# 4G.net
KiCad netlist of a schematic drawn in Altium Designer
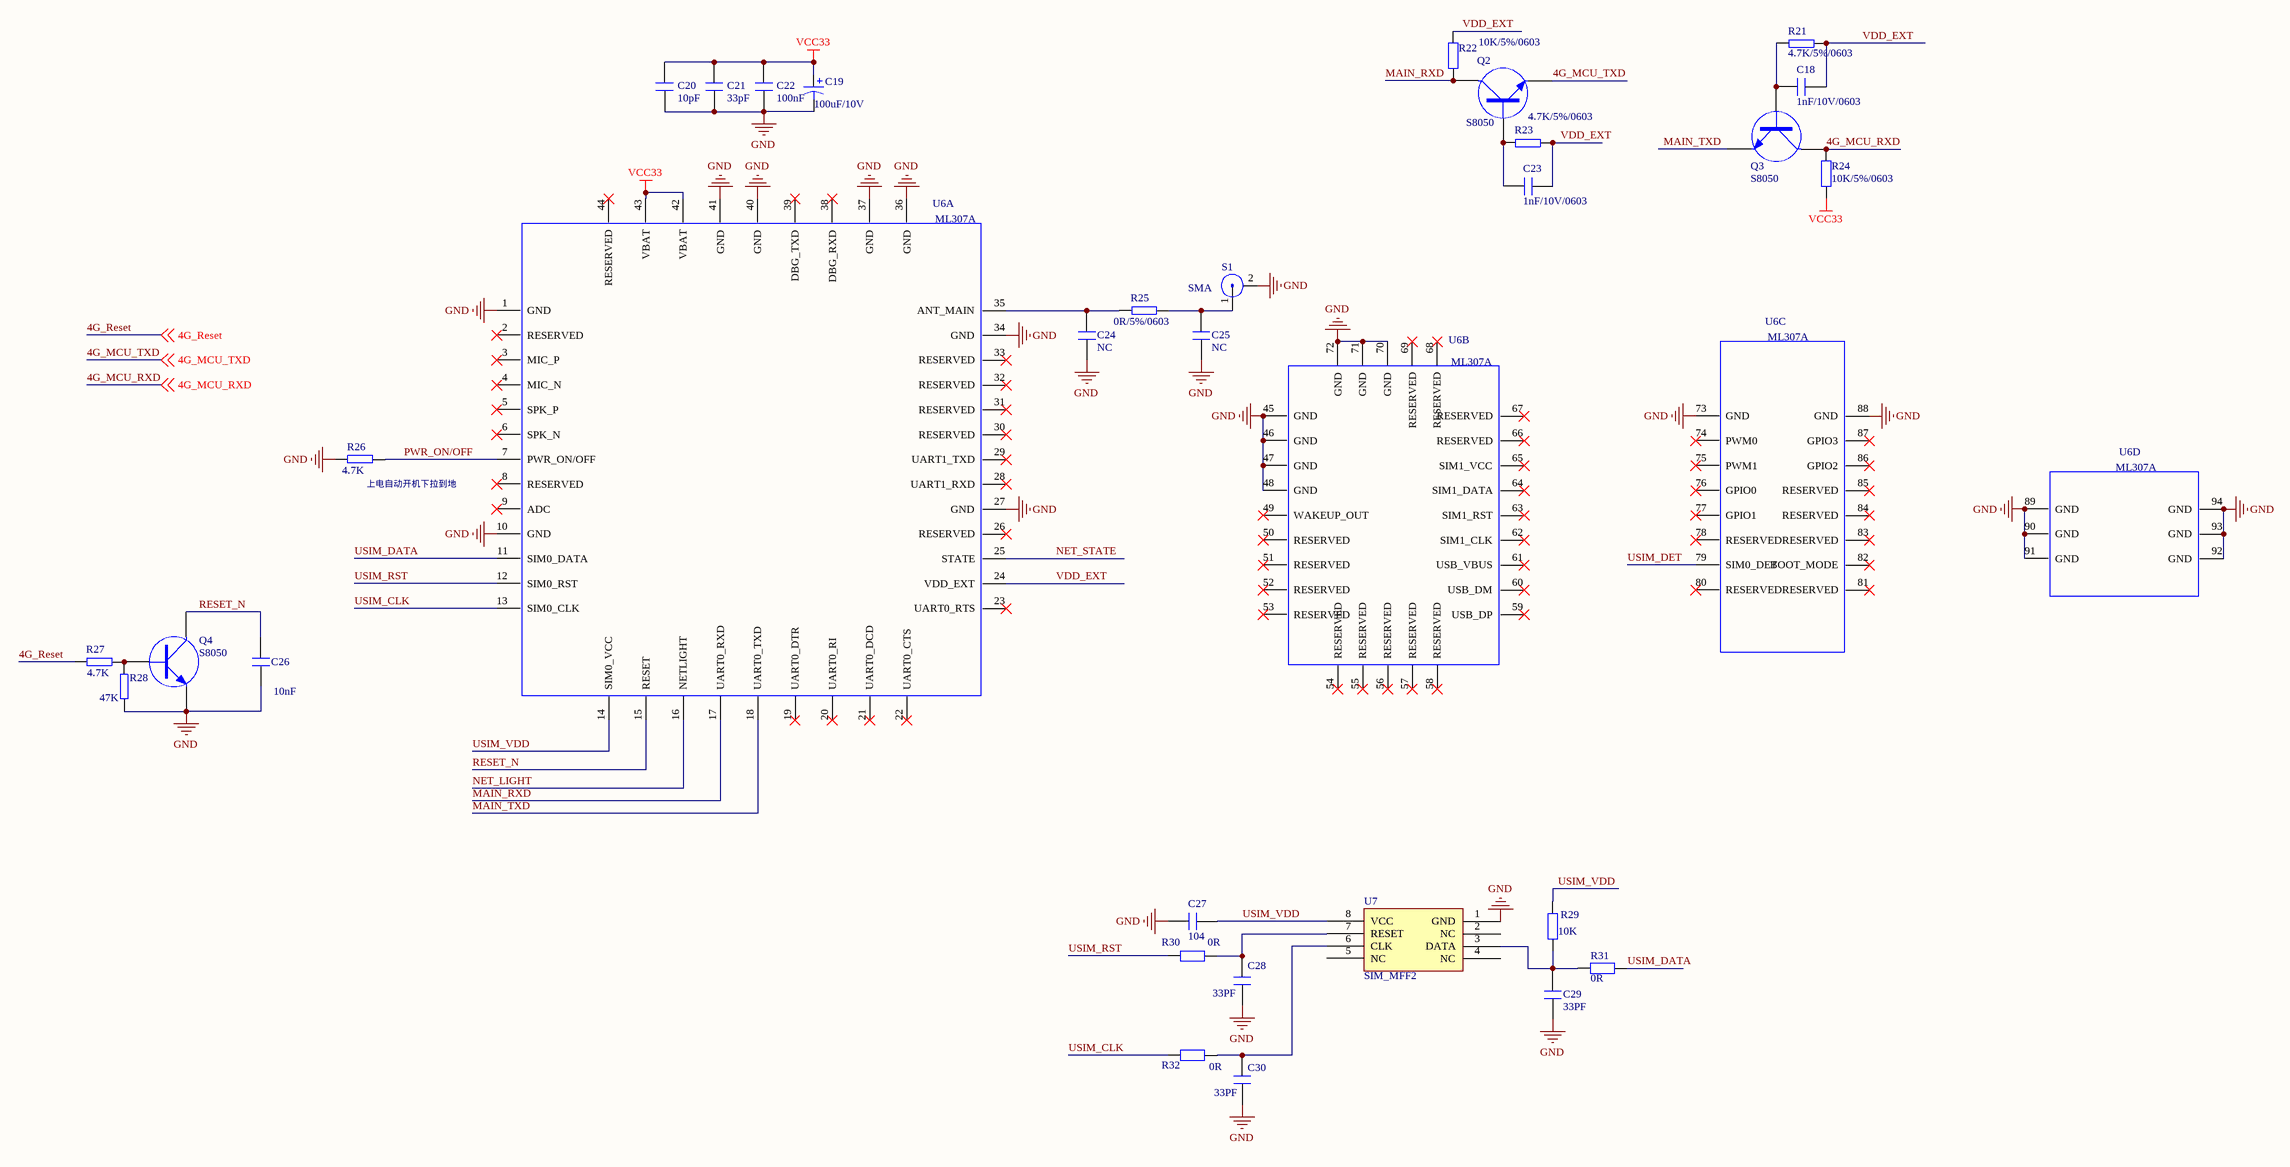
[diagram p0: 4G.SchDoc]

(export (version "E")
  (design (tool "Eeschema 10.0.6"))
  (components
    (comp (ref "C18")
      (value "1nF/10V/0603")
      (footprint "0603R")
      (libsource (lib "ES_Schematic") (part "CAP"))
    )
    (comp (ref "C19")
      (value "100uF/10V")
      (footprint "C1210")
      (description "Polarized Capacitor (Radial)")
      (fields (field (name "PUBLISHER") "Altium Limited"))
      (libsource (lib "Miscellaneous Devices") (part "Cap Pol1"))
    )
    (comp (ref "C20") (value "10pF") (footprint "0603R") (libsource (lib "ES_Schematic") (part "CAP_1")))
    (comp (ref "C21") (value "33pF") (footprint "0603R") (libsource (lib "ES_Schematic") (part "CAP_1")))
    (comp (ref "C22") (value "100nF") (footprint "0603R") (libsource (lib "ES_Schematic") (part "CAP_1")))
    (comp (ref "C23")
      (value "1nF/10V/0603")
      (footprint "0603R")
      (libsource (lib "ES_Schematic") (part "CAP"))
    )
    (comp (ref "C24") (value "NC") (footprint "0603R") (libsource (lib "ES_Schematic") (part "CAP")))
    (comp (ref "C25") (value "NC") (footprint "0603R") (libsource (lib "ES_Schematic") (part "CAP")))
    (comp (ref "C26") (value "10nF") (footprint "0603R") (libsource (lib "ES_Schematic") (part "CAP_1")))
    (comp (ref "C27") (value "104") (footprint "0603R") (libsource (lib "ES_Schematic") (part "CAP")))
    (comp (ref "C28") (value "33PF") (footprint "0603R") (libsource (lib "ES_Schematic") (part "CAP")))
    (comp (ref "C29") (value "33PF") (footprint "0603R") (libsource (lib "ES_Schematic") (part "CAP")))
    (comp (ref "C30") (value "33PF") (footprint "0603R") (libsource (lib "ES_Schematic") (part "CAP")))
    (comp (ref "Q2") (value "S8050") (footprint "SOT-23") (libsource (lib "ES_Schematic") (part "NPN")))
    (comp (ref "Q3") (value "S8050") (footprint "SOT-23") (libsource (lib "ES_Schematic") (part "NPN")))
    (comp (ref "Q4") (value "S8050") (footprint "SOT-23") (libsource (lib "ES_Schematic") (part "NPN")))
    (comp (ref "R21")
      (value "4.7K/5%/0603")
      (footprint "0603R")
      (libsource (lib "ES_Schematic") (part "RES"))
    )
    (comp (ref "R22")
      (value "10K/5%/0603")
      (footprint "0603R")
      (description "Resistor")
      (fields (field (name "PUBLISHER") "Altium Limited"))
      (libsource (lib "Miscellaneous Devices") (part "Res2"))
    )
    (comp (ref "R23")
      (value "4.7K/5%/0603")
      (footprint "0603R")
      (libsource (lib "ES_Schematic") (part "RES"))
    )
    (comp (ref "R24")
      (value "10K/5%/0603")
      (footprint "0603R")
      (description "Resistor")
      (fields (field (name "PUBLISHER") "Altium Limited"))
      (libsource (lib "Miscellaneous Devices") (part "Res2"))
    )
    (comp (ref "R25") (value "0R/5%/0603") (footprint "0603R") (libsource (lib "ES_Schematic") (part "RES")))
    (comp (ref "R26") (value "4.7K") (footprint "0603R") (libsource (lib "ES_Schematic") (part "RES")))
    (comp (ref "R27") (value "4.7K") (footprint "0603R") (libsource (lib "ES_Schematic") (part "RES")))
    (comp (ref "R28") (value "47K") (footprint "0603R") (libsource (lib "ES_Schematic") (part "RES")))
    (comp (ref "R29")
      (value "10K")
      (footprint "0603R")
      (description "Resistor")
      (fields (field (name "PUBLISHER") "Altium Limited"))
      (libsource (lib "Miscellaneous Devices") (part "Res2"))
    )
    (comp (ref "R30")
      (value "0R")
      (footprint "0603R")
      (description "Resistor")
      (fields (field (name "PUBLISHER") "Altium Limited"))
      (libsource (lib "") (part "Res2_1"))
    )
    (comp (ref "R31")
      (value "0R")
      (footprint "0603R")
      (description "Resistor")
      (fields (field (name "PUBLISHER") "Altium Limited"))
      (libsource (lib "") (part "Res2_1"))
    )
    (comp (ref "R32")
      (value "0R")
      (footprint "0603R")
      (description "Resistor")
      (fields (field (name "PUBLISHER") "Altium Limited"))
      (libsource (lib "") (part "Res2_1"))
    )
    (comp (ref "S1") (value "SMA") (footprint "RF1-00283天线座") (libsource (lib "ES_Schematic") (part "SMA")))
    (comp (ref "U6") (value "ML307A") (footprint "ML307A") (libsource (lib "*") (part "ML307A")))
    (comp (ref "U7")
      (value "SIM_MFF2")
      (footprint "VQFN8")
      (libsource (lib "ES_Schematic") (part "SIM_MFF2"))
    )
  )
  (nets
    (net (code "1") (name "/MAIN_RXD") (class "Default")
      (node (ref "Q2") (pin "3") (pinfunction "C_3") (pintype "passive"))
      (node (ref "R22") (pin "2") (pinfunction "2_2") (pintype "passive"))
      (node (ref "U6") (pin "17") (pinfunction "UART0_RXD_17") (pintype "passive"))
    )
    (net (code "2") (name "/MAIN_TXD") (class "Default")
      (node (ref "Q3") (pin "2") (pinfunction "E_2") (pintype "passive"))
      (node (ref "U6") (pin "18") (pinfunction "UART0_TXD_18") (pintype "passive"))
    )
    (net (code "3") (name "/NET_LIGHT") (class "Default")
      (node (ref "U6") (pin "16") (pinfunction "NETLIGHT_16") (pintype "passive"))
    )
    (net (code "4") (name "/NET_STATE") (class "Default")
      (node (ref "U6") (pin "25") (pinfunction "STATE_25") (pintype "passive"))
    )
    (net (code "5") (name "/PWR_ON{slash}OFF") (class "Default")
      (node (ref "R26") (pin "1") (pinfunction "1_1") (pintype "passive"))
      (node (ref "U6") (pin "7") (pinfunction "PWR_ON/OFF_7") (pintype "passive"))
    )
    (net (code "6") (name "/RESET_N") (class "Default")
      (node (ref "C26") (pin "2") (pinfunction "2_2") (pintype "passive"))
      (node (ref "Q4") (pin "3") (pinfunction "C_3") (pintype "passive"))
      (node (ref "U6") (pin "15") (pinfunction "RESET_15") (pintype "passive"))
    )
    (net (code "7") (name "/USIM_CLK") (class "Default")
      (node (ref "R32") (pin "2") (pinfunction "2_2") (pintype "passive"))
      (node (ref "U6") (pin "13") (pinfunction "SIM0_CLK_13") (pintype "passive"))
    )
    (net (code "8") (name "/USIM_DATA") (class "Default")
      (node (ref "R31") (pin "1") (pinfunction "1_1") (pintype "passive"))
      (node (ref "U6") (pin "11") (pinfunction "SIM0_DATA_11") (pintype "passive"))
    )
    (net (code "9") (name "/USIM_DET") (class "Default")
      (node (ref "U6") (pin "79") (pinfunction "SIM0_DET_79") (pintype "passive"))
    )
    (net (code "10") (name "/USIM_RST") (class "Default")
      (node (ref "R30") (pin "2") (pinfunction "2_2") (pintype "passive"))
      (node (ref "U6") (pin "12") (pinfunction "SIM0_RST_12") (pintype "passive"))
    )
    (net (code "11") (name "/USIM_VDD") (class "Default")
      (node (ref "C27") (pin "2") (pinfunction "2_2") (pintype "passive"))
      (node (ref "R29") (pin "1") (pinfunction "1_1") (pintype "passive"))
      (node (ref "U6") (pin "14") (pinfunction "SIM0_VCC_14") (pintype "passive"))
      (node (ref "U7") (pin "8") (pinfunction "VCC_8") (pintype "passive"))
    )
    (net (code "12") (name "/VDD_EXT") (class "Default")
      (node (ref "C18") (pin "2") (pinfunction "2_2") (pintype "passive"))
      (node (ref "C23") (pin "2") (pinfunction "2_2") (pintype "passive"))
      (node (ref "R21") (pin "2") (pinfunction "2_2") (pintype "passive"))
      (node (ref "R22") (pin "1") (pinfunction "1_1") (pintype "passive"))
      (node (ref "R23") (pin "2") (pinfunction "2_2") (pintype "passive"))
      (node (ref "U6") (pin "24") (pinfunction "VDD_EXT_24") (pintype "passive"))
    )
    (net (code "13") (name "4G_MCU_RXD") (class "Default")
      (node (ref "Q3") (pin "3") (pinfunction "C_3") (pintype "passive"))
      (node (ref "R24") (pin "1") (pinfunction "1_1") (pintype "passive"))
    )
    (net (code "14") (name "4G_MCU_TXD") (class "Default")
      (node (ref "Q2") (pin "2") (pinfunction "E_2") (pintype "passive"))
    )
    (net (code "15") (name "4G_Reset") (class "Default")
      (node (ref "R27") (pin "1") (pinfunction "1_1") (pintype "passive"))
    )
    (net (code "16") (name "GND") (class "Default")
      (node (ref "C19") (pin "2") (pinfunction "2_2") (pintype "passive"))
      (node (ref "C20") (pin "2") (pinfunction "2_2") (pintype "passive"))
      (node (ref "C21") (pin "2") (pinfunction "2_2") (pintype "passive"))
      (node (ref "C22") (pin "2") (pinfunction "2_2") (pintype "passive"))
      (node (ref "C24") (pin "1") (pinfunction "1_1") (pintype "passive"))
      (node (ref "C25") (pin "1") (pinfunction "1_1") (pintype "passive"))
      (node (ref "C26") (pin "1") (pinfunction "1_1") (pintype "passive"))
      (node (ref "C27") (pin "1") (pinfunction "1_1") (pintype "passive"))
      (node (ref "C28") (pin "2") (pinfunction "2_2") (pintype "passive"))
      (node (ref "C29") (pin "1") (pinfunction "1_1") (pintype "passive"))
      (node (ref "C30") (pin "2") (pinfunction "2_2") (pintype "passive"))
      (node (ref "Q4") (pin "2") (pinfunction "E_2") (pintype "passive"))
      (node (ref "R26") (pin "2") (pinfunction "2_2") (pintype "passive"))
      (node (ref "R28") (pin "2") (pinfunction "2_2") (pintype "passive"))
      (node (ref "S1") (pin "2") (pinfunction "2_2") (pintype "passive"))
      (node (ref "U6") (pin "1") (pinfunction "GND_1") (pintype "passive"))
      (node (ref "U6") (pin "10") (pinfunction "GND_10") (pintype "passive"))
      (node (ref "U6") (pin "27") (pinfunction "GND_27") (pintype "passive"))
      (node (ref "U6") (pin "34") (pinfunction "GND_34") (pintype "passive"))
      (node (ref "U6") (pin "36") (pinfunction "GND_36") (pintype "passive"))
      (node (ref "U6") (pin "37") (pinfunction "GND_37") (pintype "passive"))
      (node (ref "U6") (pin "40") (pinfunction "GND_40") (pintype "passive"))
      (node (ref "U6") (pin "41") (pinfunction "GND_41") (pintype "passive"))
      (node (ref "U6") (pin "45") (pinfunction "GND_45") (pintype "passive"))
      (node (ref "U6") (pin "46") (pinfunction "GND_46") (pintype "passive"))
      (node (ref "U6") (pin "47") (pinfunction "GND_47") (pintype "passive"))
      (node (ref "U6") (pin "48") (pinfunction "GND_48") (pintype "passive"))
      (node (ref "U6") (pin "70") (pinfunction "GND_70") (pintype "passive"))
      (node (ref "U6") (pin "71") (pinfunction "GND_71") (pintype "passive"))
      (node (ref "U6") (pin "72") (pinfunction "GND_72") (pintype "passive"))
      (node (ref "U6") (pin "73") (pinfunction "GND_73") (pintype "passive"))
      (node (ref "U6") (pin "88") (pinfunction "GND_88") (pintype "passive"))
      (node (ref "U6") (pin "89") (pinfunction "GND_89") (pintype "passive"))
      (node (ref "U6") (pin "90") (pinfunction "GND_90") (pintype "passive"))
      (node (ref "U6") (pin "91") (pinfunction "GND_91") (pintype "passive"))
      (node (ref "U6") (pin "92") (pinfunction "GND_92") (pintype "passive"))
      (node (ref "U6") (pin "93") (pinfunction "GND_93") (pintype "passive"))
      (node (ref "U6") (pin "94") (pinfunction "GND_94") (pintype "passive"))
      (node (ref "U7") (pin "1") (pinfunction "GND_1") (pintype "passive"))
    )
    (net (code "17") (name "Net-(C25-Pad2)") (class "Default")
      (node (ref "C25") (pin "2") (pinfunction "2_2") (pintype "passive"))
      (node (ref "R25") (pin "2") (pinfunction "2_2") (pintype "passive"))
      (node (ref "S1") (pin "1") (pinfunction "1_1") (pintype "passive"))
    )
    (net (code "18") (name "Net-(Q2-B)") (class "Default")
      (node (ref "C23") (pin "1") (pinfunction "1_1") (pintype "passive"))
      (node (ref "Q2") (pin "1") (pinfunction "B_1") (pintype "passive"))
      (node (ref "R23") (pin "1") (pinfunction "1_1") (pintype "passive"))
    )
    (net (code "19") (name "Net-(Q3-B)") (class "Default")
      (node (ref "C18") (pin "1") (pinfunction "1_1") (pintype "passive"))
      (node (ref "Q3") (pin "1") (pinfunction "B_1") (pintype "passive"))
      (node (ref "R21") (pin "1") (pinfunction "1_1") (pintype "passive"))
    )
    (net (code "20") (name "Net-(Q4-B)") (class "Default")
      (node (ref "Q4") (pin "1") (pinfunction "B_1") (pintype "passive"))
      (node (ref "R27") (pin "2") (pinfunction "2_2") (pintype "passive"))
      (node (ref "R28") (pin "1") (pinfunction "1_1") (pintype "passive"))
    )
    (net (code "21") (name "Net-(U6A-ANT_MAIN)") (class "Default")
      (node (ref "C24") (pin "2") (pinfunction "2_2") (pintype "passive"))
      (node (ref "R25") (pin "1") (pinfunction "1_1") (pintype "passive"))
      (node (ref "U6") (pin "35") (pinfunction "ANT_MAIN_35") (pintype "passive"))
    )
    (net (code "22") (name "Net-(U7-CLK)") (class "Default")
      (node (ref "C30") (pin "1") (pinfunction "1_1") (pintype "passive"))
      (node (ref "R32") (pin "1") (pinfunction "1_1") (pintype "passive"))
      (node (ref "U7") (pin "6") (pinfunction "CLK_6") (pintype "passive"))
    )
    (net (code "23") (name "Net-(U7-DATA)") (class "Default")
      (node (ref "C29") (pin "2") (pinfunction "2_2") (pintype "passive"))
      (node (ref "R29") (pin "2") (pinfunction "2_2") (pintype "passive"))
      (node (ref "R31") (pin "2") (pinfunction "2_2") (pintype "passive"))
      (node (ref "U7") (pin "3") (pinfunction "DATA_3") (pintype "passive"))
    )
    (net (code "24") (name "Net-(U7-RESET)") (class "Default")
      (node (ref "C28") (pin "1") (pinfunction "1_1") (pintype "passive"))
      (node (ref "R30") (pin "1") (pinfunction "1_1") (pintype "passive"))
      (node (ref "U7") (pin "7") (pinfunction "RESET_7") (pintype "passive"))
    )
    (net (code "25") (name "VCC33") (class "Default")
      (node (ref "C19") (pin "1") (pinfunction "1_1") (pintype "passive"))
      (node (ref "C20") (pin "1") (pinfunction "1_1") (pintype "passive"))
      (node (ref "C21") (pin "1") (pinfunction "1_1") (pintype "passive"))
      (node (ref "C22") (pin "1") (pinfunction "1_1") (pintype "passive"))
      (node (ref "R24") (pin "2") (pinfunction "2_2") (pintype "passive"))
      (node (ref "U6") (pin "42") (pinfunction "VBAT_42") (pintype "passive"))
      (node (ref "U6") (pin "43") (pinfunction "VBAT_43") (pintype "passive"))
    )
    (net (code "26") (name "unconnected-(U6A-ADC-Pad9)") (class "Default")
      (node (ref "U6") (pin "9") (pinfunction "ADC_9") (pintype "passive+no_connect"))
    )
    (net (code "27") (name "unconnected-(U6A-DBG_RXD-Pad38)") (class "Default")
      (node (ref "U6") (pin "38") (pinfunction "DBG_RXD_38") (pintype "passive+no_connect"))
    )
    (net (code "28") (name "unconnected-(U6A-DBG_TXD-Pad39)") (class "Default")
      (node (ref "U6") (pin "39") (pinfunction "DBG_TXD_39") (pintype "passive+no_connect"))
    )
    (net (code "29") (name "unconnected-(U6A-MIC_N-Pad4)") (class "Default")
      (node (ref "U6") (pin "4") (pinfunction "MIC_N_4") (pintype "passive+no_connect"))
    )
    (net (code "30") (name "unconnected-(U6A-MIC_P-Pad3)") (class "Default")
      (node (ref "U6") (pin "3") (pinfunction "MIC_P_3") (pintype "passive+no_connect"))
    )
    (net (code "31") (name "unconnected-(U6A-RESERVED-Pad2)") (class "Default")
      (node (ref "U6") (pin "2") (pinfunction "RESERVED_2") (pintype "passive+no_connect"))
    )
    (net (code "32") (name "unconnected-(U6A-RESERVED-Pad8)") (class "Default")
      (node (ref "U6") (pin "8") (pinfunction "RESERVED_8") (pintype "passive+no_connect"))
    )
    (net (code "33") (name "unconnected-(U6A-RESERVED-Pad26)") (class "Default")
      (node (ref "U6") (pin "26") (pinfunction "RESERVED_26") (pintype "passive+no_connect"))
    )
    (net (code "34") (name "unconnected-(U6A-RESERVED-Pad30)") (class "Default")
      (node (ref "U6") (pin "30") (pinfunction "RESERVED_30") (pintype "passive+no_connect"))
    )
    (net (code "35") (name "unconnected-(U6A-RESERVED-Pad31)") (class "Default")
      (node (ref "U6") (pin "31") (pinfunction "RESERVED_31") (pintype "passive+no_connect"))
    )
    (net (code "36") (name "unconnected-(U6A-RESERVED-Pad32)") (class "Default")
      (node (ref "U6") (pin "32") (pinfunction "RESERVED_32") (pintype "passive+no_connect"))
    )
    (net (code "37") (name "unconnected-(U6A-RESERVED-Pad33)") (class "Default")
      (node (ref "U6") (pin "33") (pinfunction "RESERVED_33") (pintype "passive+no_connect"))
    )
    (net (code "38") (name "unconnected-(U6A-RESERVED-Pad44)") (class "Default")
      (node (ref "U6") (pin "44") (pinfunction "RESERVED_44") (pintype "passive+no_connect"))
    )
    (net (code "39") (name "unconnected-(U6A-SPK_N-Pad6)") (class "Default")
      (node (ref "U6") (pin "6") (pinfunction "SPK_N_6") (pintype "passive+no_connect"))
    )
    (net (code "40") (name "unconnected-(U6A-SPK_P-Pad5)") (class "Default")
      (node (ref "U6") (pin "5") (pinfunction "SPK_P_5") (pintype "passive+no_connect"))
    )
    (net (code "41") (name "unconnected-(U6A-UART0_CTS-Pad22)") (class "Default")
      (node (ref "U6") (pin "22") (pinfunction "UART0_CTS_22") (pintype "passive+no_connect"))
    )
    (net (code "42") (name "unconnected-(U6A-UART0_DCD-Pad21)") (class "Default")
      (node (ref "U6") (pin "21") (pinfunction "UART0_DCD_21") (pintype "passive+no_connect"))
    )
    (net (code "43") (name "unconnected-(U6A-UART0_DTR-Pad19)") (class "Default")
      (node (ref "U6") (pin "19") (pinfunction "UART0_DTR_19") (pintype "passive+no_connect"))
    )
    (net (code "44") (name "unconnected-(U6A-UART0_RI-Pad20)") (class "Default")
      (node (ref "U6") (pin "20") (pinfunction "UART0_RI_20") (pintype "passive+no_connect"))
    )
    (net (code "45") (name "unconnected-(U6A-UART0_RTS-Pad23)") (class "Default")
      (node (ref "U6") (pin "23") (pinfunction "UART0_RTS_23") (pintype "passive+no_connect"))
    )
    (net (code "46") (name "unconnected-(U6A-UART1_RXD-Pad28)") (class "Default")
      (node (ref "U6") (pin "28") (pinfunction "UART1_RXD_28") (pintype "passive+no_connect"))
    )
    (net (code "47") (name "unconnected-(U6A-UART1_TXD-Pad29)") (class "Default")
      (node (ref "U6") (pin "29") (pinfunction "UART1_TXD_29") (pintype "passive+no_connect"))
    )
    (net (code "48") (name "unconnected-(U6B-RESERVED-Pad50)") (class "Default")
      (node (ref "U6") (pin "50") (pinfunction "RESERVED_50") (pintype "passive+no_connect"))
    )
    (net (code "49") (name "unconnected-(U6B-RESERVED-Pad51)") (class "Default")
      (node (ref "U6") (pin "51") (pinfunction "RESERVED_51") (pintype "passive+no_connect"))
    )
    (net (code "50") (name "unconnected-(U6B-RESERVED-Pad52)") (class "Default")
      (node (ref "U6") (pin "52") (pinfunction "RESERVED_52") (pintype "passive+no_connect"))
    )
    (net (code "51") (name "unconnected-(U6B-RESERVED-Pad53)") (class "Default")
      (node (ref "U6") (pin "53") (pinfunction "RESERVED_53") (pintype "passive+no_connect"))
    )
    (net (code "52") (name "unconnected-(U6B-RESERVED-Pad54)") (class "Default")
      (node (ref "U6") (pin "54") (pinfunction "RESERVED_54") (pintype "passive+no_connect"))
    )
    (net (code "53") (name "unconnected-(U6B-RESERVED-Pad55)") (class "Default")
      (node (ref "U6") (pin "55") (pinfunction "RESERVED_55") (pintype "passive+no_connect"))
    )
    (net (code "54") (name "unconnected-(U6B-RESERVED-Pad56)") (class "Default")
      (node (ref "U6") (pin "56") (pinfunction "RESERVED_56") (pintype "passive+no_connect"))
    )
    (net (code "55") (name "unconnected-(U6B-RESERVED-Pad57)") (class "Default")
      (node (ref "U6") (pin "57") (pinfunction "RESERVED_57") (pintype "passive+no_connect"))
    )
    (net (code "56") (name "unconnected-(U6B-RESERVED-Pad58)") (class "Default")
      (node (ref "U6") (pin "58") (pinfunction "RESERVED_58") (pintype "passive+no_connect"))
    )
    (net (code "57") (name "unconnected-(U6B-RESERVED-Pad66)") (class "Default")
      (node (ref "U6") (pin "66") (pinfunction "RESERVED_66") (pintype "passive+no_connect"))
    )
    (net (code "58") (name "unconnected-(U6B-RESERVED-Pad67)") (class "Default")
      (node (ref "U6") (pin "67") (pinfunction "RESERVED_67") (pintype "passive+no_connect"))
    )
    (net (code "59") (name "unconnected-(U6B-RESERVED-Pad68)") (class "Default")
      (node (ref "U6") (pin "68") (pinfunction "RESERVED_68") (pintype "passive+no_connect"))
    )
    (net (code "60") (name "unconnected-(U6B-RESERVED-Pad69)") (class "Default")
      (node (ref "U6") (pin "69") (pinfunction "RESERVED_69") (pintype "passive+no_connect"))
    )
    (net (code "61") (name "unconnected-(U6B-SIM1_CLK-Pad62)") (class "Default")
      (node (ref "U6") (pin "62") (pinfunction "SIM1_CLK_62") (pintype "passive+no_connect"))
    )
    (net (code "62") (name "unconnected-(U6B-SIM1_DATA-Pad64)") (class "Default")
      (node (ref "U6") (pin "64") (pinfunction "SIM1_DATA_64") (pintype "passive+no_connect"))
    )
    (net (code "63") (name "unconnected-(U6B-SIM1_RST-Pad63)") (class "Default")
      (node (ref "U6") (pin "63") (pinfunction "SIM1_RST_63") (pintype "passive+no_connect"))
    )
    (net (code "64") (name "unconnected-(U6B-SIM1_VCC-Pad65)") (class "Default")
      (node (ref "U6") (pin "65") (pinfunction "SIM1_VCC_65") (pintype "passive+no_connect"))
    )
    (net (code "65") (name "unconnected-(U6B-USB_DM-Pad60)") (class "Default")
      (node (ref "U6") (pin "60") (pinfunction "USB_DM_60") (pintype "passive+no_connect"))
    )
    (net (code "66") (name "unconnected-(U6B-USB_DP-Pad59)") (class "Default")
      (node (ref "U6") (pin "59") (pinfunction "USB_DP_59") (pintype "passive+no_connect"))
    )
    (net (code "67") (name "unconnected-(U6B-USB_VBUS-Pad61)") (class "Default")
      (node (ref "U6") (pin "61") (pinfunction "USB_VBUS_61") (pintype "passive+no_connect"))
    )
    (net (code "68") (name "unconnected-(U6B-WAKEUP_OUT-Pad49)") (class "Default")
      (node (ref "U6") (pin "49") (pinfunction "WAKEUP_OUT_49") (pintype "passive+no_connect"))
    )
    (net (code "69") (name "unconnected-(U6C-BOOT_MODE-Pad82)") (class "Default")
      (node (ref "U6") (pin "82") (pinfunction "BOOT_MODE_82") (pintype "passive+no_connect"))
    )
    (net (code "70") (name "unconnected-(U6C-GPIO0-Pad76)") (class "Default")
      (node (ref "U6") (pin "76") (pinfunction "GPIO0_76") (pintype "passive+no_connect"))
    )
    (net (code "71") (name "unconnected-(U6C-GPIO1-Pad77)") (class "Default")
      (node (ref "U6") (pin "77") (pinfunction "GPIO1_77") (pintype "passive+no_connect"))
    )
    (net (code "72") (name "unconnected-(U6C-GPIO2-Pad86)") (class "Default")
      (node (ref "U6") (pin "86") (pinfunction "GPIO2_86") (pintype "passive+no_connect"))
    )
    (net (code "73") (name "unconnected-(U6C-GPIO3-Pad87)") (class "Default")
      (node (ref "U6") (pin "87") (pinfunction "GPIO3_87") (pintype "passive+no_connect"))
    )
    (net (code "74") (name "unconnected-(U6C-PWM0-Pad74)") (class "Default")
      (node (ref "U6") (pin "74") (pinfunction "PWM0_74") (pintype "passive+no_connect"))
    )
    (net (code "75") (name "unconnected-(U6C-PWM1-Pad75)") (class "Default")
      (node (ref "U6") (pin "75") (pinfunction "PWM1_75") (pintype "passive+no_connect"))
    )
    (net (code "76") (name "unconnected-(U6C-RESERVED-Pad78)") (class "Default")
      (node (ref "U6") (pin "78") (pinfunction "RESERVED_78") (pintype "passive+no_connect"))
    )
    (net (code "77") (name "unconnected-(U6C-RESERVED-Pad80)") (class "Default")
      (node (ref "U6") (pin "80") (pinfunction "RESERVED_80") (pintype "passive+no_connect"))
    )
    (net (code "78") (name "unconnected-(U6C-RESERVED-Pad81)") (class "Default")
      (node (ref "U6") (pin "81") (pinfunction "RESERVED_81") (pintype "passive+no_connect"))
    )
    (net (code "79") (name "unconnected-(U6C-RESERVED-Pad83)") (class "Default")
      (node (ref "U6") (pin "83") (pinfunction "RESERVED_83") (pintype "passive+no_connect"))
    )
    (net (code "80") (name "unconnected-(U6C-RESERVED-Pad84)") (class "Default")
      (node (ref "U6") (pin "84") (pinfunction "RESERVED_84") (pintype "passive+no_connect"))
    )
    (net (code "81") (name "unconnected-(U6C-RESERVED-Pad85)") (class "Default")
      (node (ref "U6") (pin "85") (pinfunction "RESERVED_85") (pintype "passive+no_connect"))
    )
    (net (code "82") (name "unconnected-(U7-NC-Pad2)") (class "Default")
      (node (ref "U7") (pin "2") (pinfunction "NC_2") (pintype "passive"))
    )
    (net (code "83") (name "unconnected-(U7-NC-Pad4)") (class "Default")
      (node (ref "U7") (pin "4") (pinfunction "NC_4") (pintype "passive"))
    )
    (net (code "84") (name "unconnected-(U7-NC-Pad5)") (class "Default")
      (node (ref "U7") (pin "5") (pinfunction "NC_5") (pintype "passive"))
    )
  )
)
